# leds.net
KiCad netlist of a schematic drawn in EAGLE
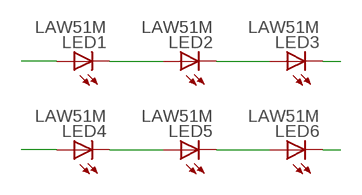
[diagram p0: schematic, sheet 1]

(export (version "E")
  (design (tool "Eeschema 10.0.6"))
  (components
    (comp (ref "LED1")
      (value "LAW51M")
      (footprint "eagle-import:W51")
      (libsource (lib "eagle-import") (part "W51MLA"))
    )
    (comp (ref "LED2")
      (value "LAW51M")
      (footprint "eagle-import:W51")
      (libsource (lib "eagle-import") (part "W51MLA"))
    )
    (comp (ref "LED3")
      (value "LAW51M")
      (footprint "eagle-import:W51")
      (libsource (lib "eagle-import") (part "W51MLA"))
    )
    (comp (ref "LED4")
      (value "LAW51M")
      (footprint "eagle-import:W51")
      (libsource (lib "eagle-import") (part "W51MLA"))
    )
    (comp (ref "LED5")
      (value "LAW51M")
      (footprint "eagle-import:W51")
      (libsource (lib "eagle-import") (part "W51MLA"))
    )
    (comp (ref "LED6")
      (value "LAW51M")
      (footprint "eagle-import:W51")
      (libsource (lib "eagle-import") (part "W51MLA"))
    )
  )
  (nets
    (net (code "1") (name "Net-(LED1-PadC)") (class "Default")
      (node (ref "LED1") (pin "C") (pinfunction "C_C") (pintype "passive"))
      (node (ref "LED2") (pin "A") (pinfunction "A_A") (pintype "passive"))
    )
    (net (code "2") (name "Net-(LED2-PadC)") (class "Default")
      (node (ref "LED2") (pin "C") (pinfunction "C_C") (pintype "passive"))
      (node (ref "LED3") (pin "A") (pinfunction "A_A") (pintype "passive"))
    )
    (net (code "3") (name "Net-(LED4-PadC)") (class "Default")
      (node (ref "LED4") (pin "C") (pinfunction "C_C") (pintype "passive"))
      (node (ref "LED5") (pin "A") (pinfunction "A_A") (pintype "passive"))
    )
    (net (code "4") (name "Net-(LED5-PadC)") (class "Default")
      (node (ref "LED5") (pin "C") (pinfunction "C_C") (pintype "passive"))
      (node (ref "LED6") (pin "A") (pinfunction "A_A") (pintype "passive"))
    )
    (net (code "5") (name "unconnected-(LED1-PadA)") (class "Default")
      (node (ref "LED1") (pin "A") (pinfunction "A_A") (pintype "passive"))
    )
    (net (code "6") (name "unconnected-(LED3-PadC)") (class "Default")
      (node (ref "LED3") (pin "C") (pinfunction "C_C") (pintype "passive"))
    )
    (net (code "7") (name "unconnected-(LED4-PadA)") (class "Default")
      (node (ref "LED4") (pin "A") (pinfunction "A_A") (pintype "passive"))
    )
    (net (code "8") (name "unconnected-(LED6-PadC)") (class "Default")
      (node (ref "LED6") (pin "C") (pinfunction "C_C") (pintype "passive"))
    )
  )
)
